# rev02_12.net
KiCad netlist of a schematic drawn in Altium Designer
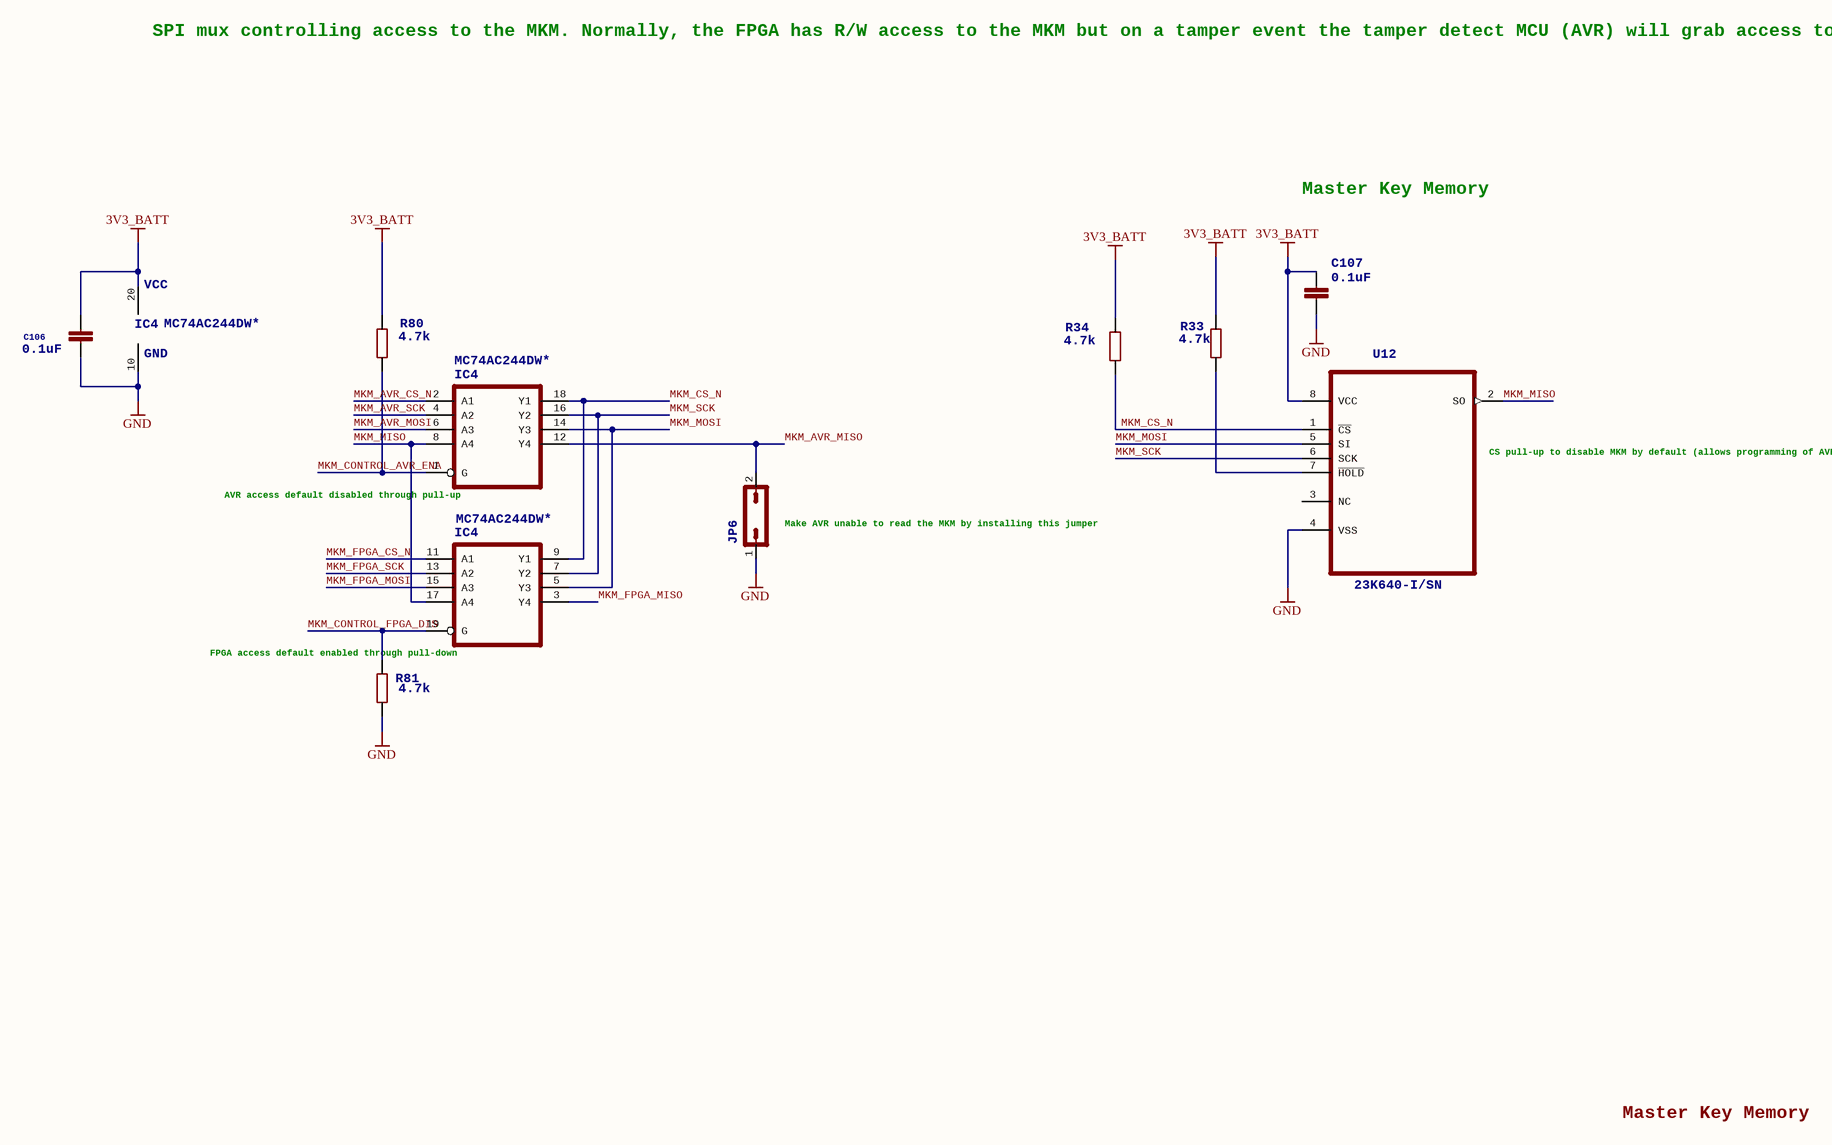
[diagram p0: rev02_12.SchDoc]

(export (version "E")
  (design (tool "Eeschema 10.0.6"))
  (components
    (comp (ref "C106")
      (value "0.1uF")
      (footprint "C_0402")
      (description "0402 CAPACITOR")
      (libsource (lib "resistor") (part "C-EUC0402"))
    )
    (comp (ref "C107")
      (value "0.1uF")
      (footprint "C_0402")
      (description "0402 CAPACITOR")
      (libsource (lib "resistor") (part "C-EUC0402"))
    )
    (comp (ref "IC4")
      (value "MC74AC244DW*")
      (footprint "SO20W")
      (description "Octal BUFFER and LINE DRIVER, 3-state")
      (fields (field (name ">NAME") "IC4") (field (name "GND") "GND") (field (name "VCC") "VCC"))
      (libsource (lib "74xx-eu") (part "74*244DW"))
    )
    (comp (ref "JP6")
      (value "61300211121")
      (footprint "PLS-2")
      (description "Wurth 2pins connector (for jumper)")
      (fields (field (name ">NAME") "JP6"))
      (libsource (lib "jumper") (part "JP1Q"))
    )
    (comp (ref "R33")
      (value "4.7k")
      (footprint "R_0402")
      (description "0402 Resistor 5%")
      (libsource (lib "resistor") (part "R-EU_R0402"))
    )
    (comp (ref "R34")
      (value "4.7k")
      (footprint "R_0402")
      (description "0402 Resistor 5%")
      (libsource (lib "resistor") (part "R-EU_R0402"))
    )
    (comp (ref "R80")
      (value "4.7k")
      (footprint "R_0402")
      (description "0402 Resistor 5%")
      (fields (field (name "TOLERANCE") "5%") (field (name ">NAME") "R80"))
      (libsource (lib "resistor") (part "R-EU_R0402"))
    )
    (comp (ref "R81")
      (value "4.7k")
      (footprint "R_0402")
      (description "0402 Resistor 5%")
      (fields (field (name "TOLERANCE") "5%") (field (name ">NAME") "R81"))
      (libsource (lib "resistor") (part "R-EU_R0402"))
    )
    (comp (ref "U12")
      (value "23K640-I/SN")
      (footprint "SOIC127P600X175-8N")
      (description "64K SPI Bus Low-Power Serial SRAM,SOIC-8")
      (fields (field (name ">NAME") "U12") (field (name ">VALUE") "23K640-I/SN"))
      (libsource (lib "Microchip-23K640-I_SN") (part "23K640-I/SN"))
    )
  )
  (nets
    (net (code "1") (name "/MKM_AVR_CS_N") (class "Default")
      (node (ref "IC4") (pin "2") (pinfunction "A1_2") (pintype "passive"))
    )
    (net (code "2") (name "/MKM_AVR_MISO") (class "Default")
      (node (ref "IC4") (pin "12") (pinfunction "Y4_12") (pintype "tri_state"))
      (node (ref "JP6") (pin "2") (pinfunction "2_2") (pintype "passive"))
    )
    (net (code "3") (name "/MKM_AVR_MOSI") (class "Default")
      (node (ref "IC4") (pin "6") (pinfunction "A3_6") (pintype "passive"))
    )
    (net (code "4") (name "/MKM_AVR_SCK") (class "Default")
      (node (ref "IC4") (pin "4") (pinfunction "A2_4") (pintype "passive"))
    )
    (net (code "5") (name "/MKM_CONTROL_AVR_ENA") (class "Default")
      (node (ref "IC4") (pin "1") (pinfunction "G_1") (pintype "passive"))
      (node (ref "R80") (pin "1") (pinfunction "1_1") (pintype "passive"))
    )
    (net (code "6") (name "/MKM_CONTROL_FPGA_DIS") (class "Default")
      (node (ref "IC4") (pin "19") (pinfunction "G_19") (pintype "passive"))
      (node (ref "R81") (pin "1") (pinfunction "1_1") (pintype "passive"))
    )
    (net (code "7") (name "/MKM_CS_N") (class "Default")
      (node (ref "IC4") (pin "18") (pinfunction "Y1_18") (pintype "tri_state"))
      (node (ref "IC4") (pin "9") (pinfunction "Y1_9") (pintype "tri_state"))
      (node (ref "R34") (pin "1") (pinfunction "1_1") (pintype "passive"))
      (node (ref "U12") (pin "1") (pinfunction "~{CS}_1") (pintype "passive"))
    )
    (net (code "8") (name "/MKM_FPGA_CS_N") (class "Default")
      (node (ref "IC4") (pin "11") (pinfunction "A1_11") (pintype "passive"))
    )
    (net (code "9") (name "/MKM_FPGA_MISO") (class "Default")
      (node (ref "IC4") (pin "3") (pinfunction "Y4_3") (pintype "tri_state"))
    )
    (net (code "10") (name "/MKM_FPGA_MOSI") (class "Default")
      (node (ref "IC4") (pin "15") (pinfunction "A3_15") (pintype "passive"))
    )
    (net (code "11") (name "/MKM_FPGA_SCK") (class "Default")
      (node (ref "IC4") (pin "13") (pinfunction "A2_13") (pintype "passive"))
    )
    (net (code "12") (name "/MKM_MISO") (class "Default")
      (node (ref "IC4") (pin "17") (pinfunction "A4_17") (pintype "passive"))
      (node (ref "IC4") (pin "8") (pinfunction "A4_8") (pintype "passive"))
      (node (ref "U12") (pin "2") (pinfunction "SO_2") (pintype "output"))
    )
    (net (code "13") (name "/MKM_MOSI") (class "Default")
      (node (ref "IC4") (pin "14") (pinfunction "Y3_14") (pintype "tri_state"))
      (node (ref "IC4") (pin "5") (pinfunction "Y3_5") (pintype "tri_state"))
      (node (ref "U12") (pin "5") (pinfunction "SI_5") (pintype "passive"))
    )
    (net (code "14") (name "/MKM_SCK") (class "Default")
      (node (ref "IC4") (pin "16") (pinfunction "Y2_16") (pintype "tri_state"))
      (node (ref "IC4") (pin "7") (pinfunction "Y2_7") (pintype "tri_state"))
      (node (ref "U12") (pin "6") (pinfunction "SCK_6") (pintype "passive"))
    )
    (net (code "15") (name "3V3_BATT") (class "Default")
      (node (ref "C106") (pin "1") (pinfunction "1_1") (pintype "passive"))
      (node (ref "C107") (pin "1") (pinfunction "1_1") (pintype "passive"))
      (node (ref "IC4") (pin "20") (pinfunction "VCC_20") (pintype "power_in"))
      (node (ref "R33") (pin "1") (pinfunction "1_1") (pintype "passive"))
      (node (ref "R34") (pin "2") (pinfunction "2_2") (pintype "passive"))
      (node (ref "R80") (pin "2") (pinfunction "2_2") (pintype "passive"))
      (node (ref "U12") (pin "8") (pinfunction "VCC_8") (pintype "power_in"))
    )
    (net (code "16") (name "GND") (class "Default")
      (node (ref "C106") (pin "2") (pinfunction "2_2") (pintype "passive"))
      (node (ref "C107") (pin "2") (pinfunction "2_2") (pintype "passive"))
      (node (ref "IC4") (pin "10") (pinfunction "GND_10") (pintype "power_in"))
      (node (ref "JP6") (pin "1") (pinfunction "1_1") (pintype "passive"))
      (node (ref "R81") (pin "2") (pinfunction "2_2") (pintype "passive"))
      (node (ref "U12") (pin "4") (pinfunction "VSS_4") (pintype "power_in"))
    )
    (net (code "17") (name "Net-(U12-~{HOLD})") (class "Default")
      (node (ref "R33") (pin "2") (pinfunction "2_2") (pintype "passive"))
      (node (ref "U12") (pin "7") (pinfunction "~{HOLD}_7") (pintype "passive"))
    )
    (net (code "18") (name "unconnected-(U12-NC-Pad3)") (class "Default")
      (node (ref "U12") (pin "3") (pinfunction "NC_3") (pintype "passive"))
    )
  )
)
